# TCS3103.net
KiCad netlist of a schematic drawn in EAGLE
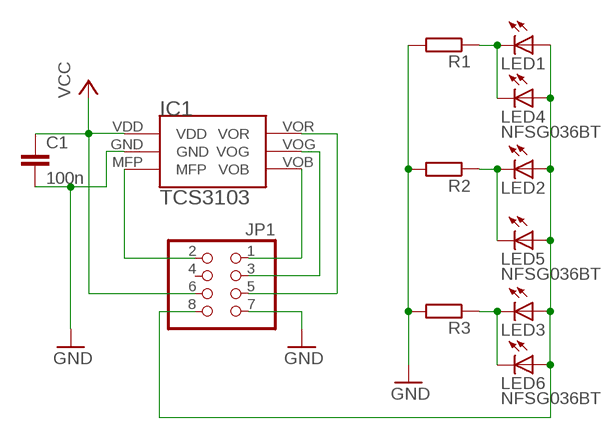
[diagram p0: schematic, sheet 1]

(export (version "E")
  (design (tool "Eeschema 10.0.6"))
  (components
    (comp (ref "C1")
      (value "100n")
      (footprint "eagle-import:C0805")
      (libsource (lib "eagle-import") (part "C-EUC0805"))
    )
    (comp (ref "IC1")
      (value "TCS3103")
      (footprint "eagle-import:TCS3103")
      (libsource (lib "eagle-import") (part "TCS3103"))
    )
    (comp (ref "JP1")
      (value "PINHD-2X4")
      (footprint "eagle-import:2X04")
      (libsource (lib "eagle-import") (part "PINHD-2X4"))
    )
    (comp (ref "LED1")
      (value "LED3MM")
      (footprint "eagle-import:LED3MM")
      (libsource (lib "eagle-import") (part "LED3MM"))
    )
    (comp (ref "LED2")
      (value "LED3MM")
      (footprint "eagle-import:LED3MM")
      (libsource (lib "eagle-import") (part "LED3MM"))
    )
    (comp (ref "LED3")
      (value "LED3MM")
      (footprint "eagle-import:LED3MM")
      (libsource (lib "eagle-import") (part "LED3MM"))
    )
    (comp (ref "LED4")
      (value "NFSG036BT")
      (footprint "eagle-import:NFSG036BT")
      (libsource (lib "eagle-import") (part "NFSG036BT"))
    )
    (comp (ref "LED5")
      (value "NFSG036BT")
      (footprint "eagle-import:NFSG036BT")
      (libsource (lib "eagle-import") (part "NFSG036BT"))
    )
    (comp (ref "LED6")
      (value "NFSG036BT")
      (footprint "eagle-import:NFSG036BT")
      (libsource (lib "eagle-import") (part "NFSG036BT"))
    )
    (comp (ref "R1")
      (value "R-EU_M0805")
      (footprint "eagle-import:M0805")
      (libsource (lib "eagle-import") (part "R-EU_M0805"))
    )
    (comp (ref "R2")
      (value "R-EU_M0805")
      (footprint "eagle-import:M0805")
      (libsource (lib "eagle-import") (part "R-EU_M0805"))
    )
    (comp (ref "R3")
      (value "R-EU_M0805")
      (footprint "eagle-import:M0805")
      (libsource (lib "eagle-import") (part "R-EU_M0805"))
    )
  )
  (nets
    (net (code "1") (name "GND") (class "Default")
      (node (ref "C1") (pin "2") (pinfunction "2_2") (pintype "passive"))
      (node (ref "IC1") (pin "GND") (pinfunction "GND_GND") (pintype "power_in"))
      (node (ref "JP1") (pin "7") (pinfunction "7_7") (pintype "passive"))
      (node (ref "R1") (pin "2") (pinfunction "2_2") (pintype "passive"))
      (node (ref "R2") (pin "2") (pinfunction "2_2") (pintype "passive"))
      (node (ref "R3") (pin "2") (pinfunction "2_2") (pintype "passive"))
    )
    (net (code "2") (name "Net-(IC1-PadMFP)") (class "Default")
      (node (ref "IC1") (pin "MFP") (pinfunction "MFP_MFP") (pintype "input"))
      (node (ref "JP1") (pin "2") (pinfunction "2_2") (pintype "passive"))
    )
    (net (code "3") (name "Net-(IC1-PadVOB)") (class "Default")
      (node (ref "IC1") (pin "VOB") (pinfunction "VOB_VOB") (pintype "output"))
      (node (ref "JP1") (pin "1") (pinfunction "1_1") (pintype "passive"))
    )
    (net (code "4") (name "Net-(IC1-PadVOG)") (class "Default")
      (node (ref "IC1") (pin "VOG") (pinfunction "VOG_VOG") (pintype "output"))
      (node (ref "JP1") (pin "3") (pinfunction "3_3") (pintype "passive"))
    )
    (net (code "5") (name "Net-(IC1-PadVOR)") (class "Default")
      (node (ref "IC1") (pin "VOR") (pinfunction "VOR_VOR") (pintype "output"))
      (node (ref "JP1") (pin "5") (pinfunction "5_5") (pintype "passive"))
    )
    (net (code "6") (name "Net-(JP1-Pad8)") (class "Default")
      (node (ref "JP1") (pin "8") (pinfunction "8_8") (pintype "passive"))
      (node (ref "LED1") (pin "A") (pinfunction "A_A") (pintype "passive"))
      (node (ref "LED2") (pin "A") (pinfunction "A_A") (pintype "passive"))
      (node (ref "LED3") (pin "A") (pinfunction "A_A") (pintype "passive"))
      (node (ref "LED4") (pin "A") (pinfunction "A_A") (pintype "passive"))
      (node (ref "LED5") (pin "A") (pinfunction "A_A") (pintype "passive"))
      (node (ref "LED6") (pin "A") (pinfunction "A_A") (pintype "passive"))
    )
    (net (code "7") (name "Net-(LED1-C)") (class "Default")
      (node (ref "LED1") (pin "K") (pinfunction "C_K") (pintype "passive"))
      (node (ref "LED4") (pin "C") (pinfunction "C_C") (pintype "passive"))
      (node (ref "R1") (pin "1") (pinfunction "1_1") (pintype "passive"))
    )
    (net (code "8") (name "Net-(LED2-C)") (class "Default")
      (node (ref "LED2") (pin "K") (pinfunction "C_K") (pintype "passive"))
      (node (ref "LED5") (pin "C") (pinfunction "C_C") (pintype "passive"))
      (node (ref "R2") (pin "1") (pinfunction "1_1") (pintype "passive"))
    )
    (net (code "9") (name "Net-(LED3-C)") (class "Default")
      (node (ref "LED3") (pin "K") (pinfunction "C_K") (pintype "passive"))
      (node (ref "LED6") (pin "C") (pinfunction "C_C") (pintype "passive"))
      (node (ref "R3") (pin "1") (pinfunction "1_1") (pintype "passive"))
    )
    (net (code "10") (name "VCC") (class "Default")
      (node (ref "C1") (pin "1") (pinfunction "1_1") (pintype "passive"))
      (node (ref "IC1") (pin "VDD") (pinfunction "VDD_VDD") (pintype "power_in"))
      (node (ref "JP1") (pin "6") (pinfunction "6_6") (pintype "passive"))
    )
    (net (code "11") (name "unconnected-(JP1-Pad4)") (class "Default")
      (node (ref "JP1") (pin "4") (pinfunction "4_4") (pintype "passive"))
    )
  )
)
